# tiny13_charlie4_50mm_boosted.net
KiCad netlist of a schematic drawn in EAGLE
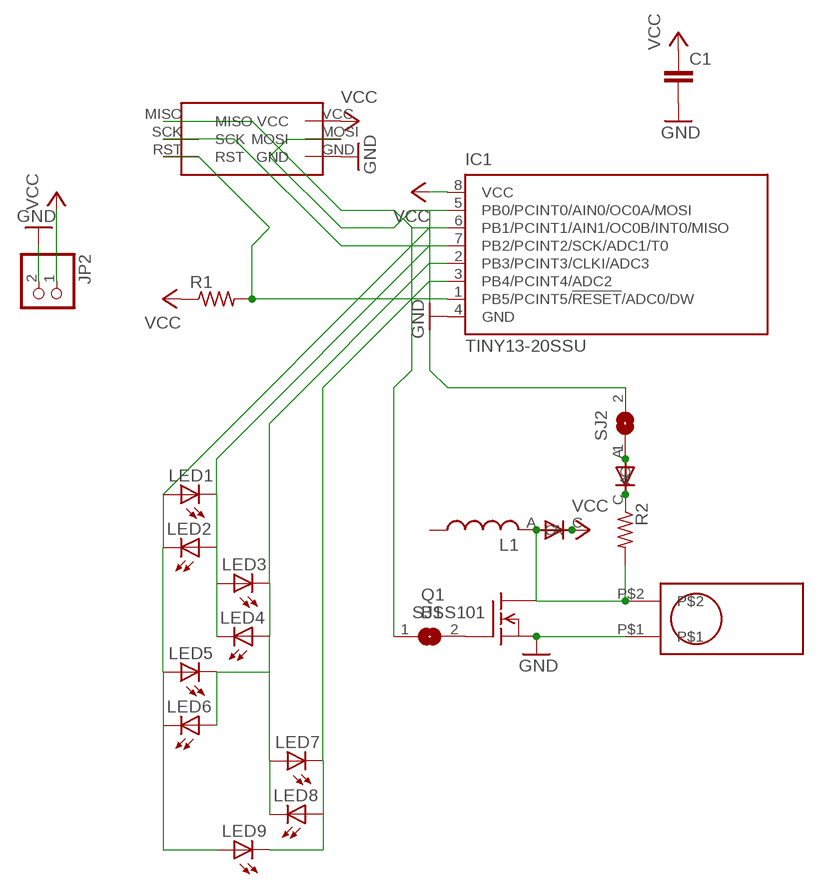
[diagram p0: schematic, sheet 1]

(export (version "E")
  (design (tool "Eeschema 10.0.6"))
  (components
    (comp (ref "C1")
      (value "C-EU025-025X050")
      (footprint "eagle-import:C025-025X050")
      (libsource (lib "eagle-import") (part "C-EU025-025X050"))
    )
    (comp (ref "IC1")
      (value "TINY13-20SSU")
      (footprint "eagle-import:8S1")
      (fields (field (name "MPN") "ATTINY13-20SSU"))
      (libsource (lib "eagle-import") (part "TINY13SSU-20"))
    )
    (comp (ref "JP2")
      (value "PINHD-1X2/90")
      (footprint "eagle-import:1X02_90")
      (libsource (lib "eagle-import") (part "PINHD-1X2/90"))
    )
    (comp (ref "L1")
      (value "L-US0207/7")
      (footprint "eagle-import:0207_7")
      (libsource (lib "eagle-import") (part "L-US0207/7"))
    )
    (comp (ref "LED1")
      (value "LED3MM")
      (footprint "eagle-import:LED3MM")
      (libsource (lib "eagle-import") (part "LED3MM"))
    )
    (comp (ref "LED2")
      (value "LED3MM")
      (footprint "eagle-import:LED3MM")
      (libsource (lib "eagle-import") (part "LED3MM"))
    )
    (comp (ref "LED3")
      (value "LED3MM")
      (footprint "eagle-import:LED3MM")
      (libsource (lib "eagle-import") (part "LED3MM"))
    )
    (comp (ref "LED4")
      (value "LED3MM")
      (footprint "eagle-import:LED3MM")
      (libsource (lib "eagle-import") (part "LED3MM"))
    )
    (comp (ref "LED5")
      (value "LED3MM")
      (footprint "eagle-import:LED3MM")
      (libsource (lib "eagle-import") (part "LED3MM"))
    )
    (comp (ref "LED6")
      (value "LED3MM")
      (footprint "eagle-import:LED3MM")
      (libsource (lib "eagle-import") (part "LED3MM"))
    )
    (comp (ref "LED7")
      (value "LED3MM")
      (footprint "eagle-import:LED3MM")
      (libsource (lib "eagle-import") (part "LED3MM"))
    )
    (comp (ref "LED8")
      (value "LED3MM")
      (footprint "eagle-import:LED3MM")
      (libsource (lib "eagle-import") (part "LED3MM"))
    )
    (comp (ref "LED9")
      (value "LED3MM")
      (footprint "eagle-import:LED3MM")
      (libsource (lib "eagle-import") (part "LED3MM"))
    )
    (comp (ref "Q1")
      (value "BSS101")
      (footprint "eagle-import:TO92")
      (libsource (lib "eagle-import") (part "BSS101"))
    )
    (comp (ref "R1")
      (value "R-US_0207/7")
      (footprint "eagle-import:0207_7")
      (libsource (lib "eagle-import") (part "R-US_0207/7"))
    )
    (comp (ref "R2")
      (value "R-US_0207/7")
      (footprint "eagle-import:0207_7")
      (libsource (lib "eagle-import") (part "R-US_0207/7"))
    )
    (comp (ref "SJ1") (value "SJ") (footprint "eagle-import:SJ") (libsource (lib "eagle-import") (part "SJ")))
    (comp (ref "SJ2") (value "SJ") (footprint "eagle-import:SJ") (libsource (lib "eagle-import") (part "SJ")))
    (comp (ref "U$1")
      (value "TILT_SWITCH_MECHANICAL")
      (footprint "eagle-import:TILT_SWITCH_MECHANICAL")
      (libsource (lib "eagle-import") (part "TILT_SWITCH_MECHANICAL"))
    )
    (comp (ref "U$2")
      (value "AVR_ISP_6_PIN_1X6_SMT_CONTACT_PROGRAMMER")
      (footprint "eagle-import:CONTACT_ISP_PROGRAMMER_1X6_ATMEL")
      (libsource (lib "eagle-import") (part "AVR_ISP_6_PIN_1X6_SMT_CONTACT_PROGRAMMER"))
    )
    (comp (ref "U$3")
      (value "D-6")
      (footprint "eagle-import:D-7.5")
      (libsource (lib "eagle-import") (part "D-6"))
    )
    (comp (ref "U$4")
      (value "D-6")
      (footprint "eagle-import:D-7.5")
      (libsource (lib "eagle-import") (part "D-6"))
    )
  )
  (nets
    (net (code "1") (name "GND") (class "Default")
      (node (ref "C1") (pin "2") (pinfunction "2_2") (pintype "passive"))
      (node (ref "IC1") (pin "4") (pinfunction "GND_4") (pintype "power_in"))
      (node (ref "JP2") (pin "2") (pinfunction "2_2") (pintype "passive"))
      (node (ref "Q1") (pin "1") (pinfunction "S_1") (pintype "passive"))
      (node (ref "U$1") (pin "P$1") (pinfunction "P$1_P$1") (pintype "bidirectional"))
      (node (ref "U$2") (pin "GND") (pinfunction "GND_GND") (pintype "bidirectional"))
    )
    (net (code "2") (name "Net-(IC1-PB0{slash}PCINT0{slash}AIN0{slash}OC0A{slash}MOSI)") (class "Default")
      (node (ref "IC1") (pin "5") (pinfunction "PB0/PCINT0/AIN0/OC0A/MOSI_5") (pintype "bidirectional"))
      (node (ref "SJ2") (pin "2") (pinfunction "2_2") (pintype "passive"))
      (node (ref "U$2") (pin "MOSI") (pinfunction "MOSI_MOSI") (pintype "bidirectional"))
    )
    (net (code "3") (name "Net-(IC1-PB1{slash}PCINT1{slash}AIN1{slash}OC0B{slash}INT0{slash}MISO)") (class "Default")
      (node (ref "IC1") (pin "6") (pinfunction "PB1/PCINT1/AIN1/OC0B/INT0/MISO_6") (pintype "bidirectional"))
      (node (ref "LED1") (pin "A") (pinfunction "A_A") (pintype "passive"))
      (node (ref "LED2") (pin "K") (pinfunction "C_K") (pintype "passive"))
      (node (ref "LED5") (pin "A") (pinfunction "A_A") (pintype "passive"))
      (node (ref "LED6") (pin "K") (pinfunction "C_K") (pintype "passive"))
      (node (ref "LED9") (pin "A") (pinfunction "A_A") (pintype "passive"))
      (node (ref "SJ1") (pin "1") (pinfunction "1_1") (pintype "passive"))
      (node (ref "U$2") (pin "MISO") (pinfunction "MISO_MISO") (pintype "bidirectional"))
    )
    (net (code "4") (name "Net-(IC1-PB2{slash}PCINT2{slash}SCK{slash}ADC1{slash}T0)") (class "Default")
      (node (ref "IC1") (pin "7") (pinfunction "PB2/PCINT2/SCK/ADC1/T0_7") (pintype "bidirectional"))
      (node (ref "LED1") (pin "K") (pinfunction "C_K") (pintype "passive"))
      (node (ref "LED2") (pin "A") (pinfunction "A_A") (pintype "passive"))
      (node (ref "LED3") (pin "A") (pinfunction "A_A") (pintype "passive"))
      (node (ref "LED4") (pin "K") (pinfunction "C_K") (pintype "passive"))
      (node (ref "U$2") (pin "SCK") (pinfunction "SCK_SCK") (pintype "bidirectional"))
    )
    (net (code "5") (name "Net-(IC1-PB3{slash}PCINT3{slash}CLKI{slash}ADC3)") (class "Default")
      (node (ref "IC1") (pin "2") (pinfunction "PB3/PCINT3/CLKI/ADC3_2") (pintype "bidirectional"))
      (node (ref "LED3") (pin "K") (pinfunction "C_K") (pintype "passive"))
      (node (ref "LED4") (pin "A") (pinfunction "A_A") (pintype "passive"))
      (node (ref "LED5") (pin "K") (pinfunction "C_K") (pintype "passive"))
      (node (ref "LED6") (pin "A") (pinfunction "A_A") (pintype "passive"))
      (node (ref "LED7") (pin "A") (pinfunction "A_A") (pintype "passive"))
      (node (ref "LED8") (pin "K") (pinfunction "C_K") (pintype "passive"))
    )
    (net (code "6") (name "Net-(IC1-PB4{slash}PCINT4{slash}ADC2)") (class "Default")
      (node (ref "IC1") (pin "3") (pinfunction "PB4/PCINT4/ADC2_3") (pintype "bidirectional"))
      (node (ref "LED7") (pin "K") (pinfunction "C_K") (pintype "passive"))
      (node (ref "LED8") (pin "A") (pinfunction "A_A") (pintype "passive"))
      (node (ref "LED9") (pin "K") (pinfunction "C_K") (pintype "passive"))
    )
    (net (code "7") (name "Net-(IC1-PB5{slash}PCINT5{slash}~{RESET}{slash}ADC0{slash}DW)") (class "Default")
      (node (ref "IC1") (pin "1") (pinfunction "PB5/PCINT5/~{RESET}/ADC0/DW_1") (pintype "bidirectional"))
      (node (ref "R1") (pin "2") (pinfunction "2_2") (pintype "passive"))
      (node (ref "U$2") (pin "RST") (pinfunction "RST_RST") (pintype "bidirectional"))
    )
    (net (code "8") (name "Net-(Q1-D)") (class "Default")
      (node (ref "L1") (pin "2") (pinfunction "2_2") (pintype "passive"))
      (node (ref "Q1") (pin "3") (pinfunction "D_3") (pintype "passive"))
      (node (ref "R2") (pin "2") (pinfunction "2_2") (pintype "passive"))
      (node (ref "U$1") (pin "P$2") (pinfunction "P$2_P$2") (pintype "bidirectional"))
      (node (ref "U$3") (pin "A") (pinfunction "A_A") (pintype "bidirectional"))
    )
    (net (code "9") (name "Net-(Q1-G)") (class "Default")
      (node (ref "Q1") (pin "2") (pinfunction "G_2") (pintype "passive"))
      (node (ref "SJ1") (pin "2") (pinfunction "2_2") (pintype "passive"))
    )
    (net (code "10") (name "Net-(R2-Pad1)") (class "Default")
      (node (ref "R2") (pin "1") (pinfunction "1_1") (pintype "passive"))
      (node (ref "U$4") (pin "C") (pinfunction "C_C") (pintype "bidirectional"))
    )
    (net (code "11") (name "Net-(SJ2-Pad1)") (class "Default")
      (node (ref "SJ2") (pin "1") (pinfunction "1_1") (pintype "passive"))
      (node (ref "U$4") (pin "A") (pinfunction "A_A") (pintype "bidirectional"))
    )
    (net (code "12") (name "VCC") (class "Default")
      (node (ref "C1") (pin "1") (pinfunction "1_1") (pintype "passive"))
      (node (ref "IC1") (pin "8") (pinfunction "VCC_8") (pintype "power_in"))
      (node (ref "JP2") (pin "1") (pinfunction "1_1") (pintype "passive"))
      (node (ref "R1") (pin "1") (pinfunction "1_1") (pintype "passive"))
      (node (ref "U$2") (pin "VCC") (pinfunction "VCC_VCC") (pintype "bidirectional"))
      (node (ref "U$3") (pin "C") (pinfunction "C_C") (pintype "bidirectional"))
    )
    (net (code "13") (name "unconnected-(L1-Pad1)") (class "Default")
      (node (ref "L1") (pin "1") (pinfunction "1_1") (pintype "passive"))
    )
  )
)
